# EEPROM.net
KiCad netlist of a schematic drawn in Altium Designer
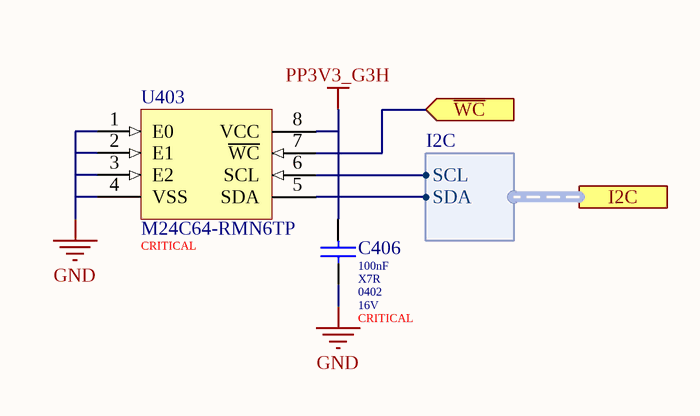
[diagram p0: EEPROM.SchDoc]

(export (version "E")
  (design (tool "Eeschema 10.0.6"))
  (components
    (comp (ref "C406")
      (value "100nF")
      (footprint "0402_050_5 (Samsumg) B")
      (description "MLCC 100nF 0402 16V X7R ±10%")
      (fields
        (field (name "DIELECTRIC") "X7R")
        (field (name "PACKAGE") "0402")
        (field (name "VOLTAGE") "16V")
        (field (name "POPULATE") "CRITICAL")
        (field (name "LCSC PART NUMBER") "C1525")
        (field (name "MANUFACTURER") "Samsung")
      )
      (libsource (lib "University of Cape Town") (part "Symbol"))
    )
    (comp (ref "U403")
      (value "M24C64-RMN6TP")
      (footprint "SO8N (M24) B")
      (description "IC EEPROM 64KBIT 1MHZ 8TSSOP")
      (fields
        (field (name "PLACEMENT") "CRITICAL")
        (field (name "LCSC PART NUMBER") "C79988")
        (field (name "MANUFACTURER") "STMicroelectronics")
      )
      (libsource (lib "University of Cape Town") (part "M24"))
    )
  )
  (nets
    (net (code "2") (name "/SCL") (class "Default")
      (node (ref "U403") (pin "6") (pinfunction "SCL_6") (pintype "input"))
    )
    (net (code "3") (name "/SDA") (class "Default")
      (node (ref "U403") (pin "5") (pinfunction "SDA_5") (pintype "open_collector"))
    )
    (net (code "4") (name "/WC") (class "Default")
      (node (ref "U403") (pin "7") (pinfunction "WC_7") (pintype "input"))
    )
    (net (code "6") (name "GND") (class "Default")
      (node (ref "C406") (pin "2") (pinfunction "2_2") (pintype "passive"))
      (node (ref "U403") (pin "1") (pinfunction "E0_1") (pintype "input"))
      (node (ref "U403") (pin "2") (pinfunction "E1_2") (pintype "input"))
      (node (ref "U403") (pin "3") (pinfunction "E2_3") (pintype "input"))
      (node (ref "U403") (pin "4") (pinfunction "VSS_4") (pintype "power_in"))
    )
    (net (code "7") (name "PP3V3_G3H") (class "Default")
      (node (ref "C406") (pin "1") (pinfunction "1_1") (pintype "passive"))
      (node (ref "U403") (pin "8") (pinfunction "VCC_8") (pintype "power_in"))
    )
  )
)
